# B293A_CoX_Amp_Top.net
KiCad netlist of a schematic drawn in Altium Designer
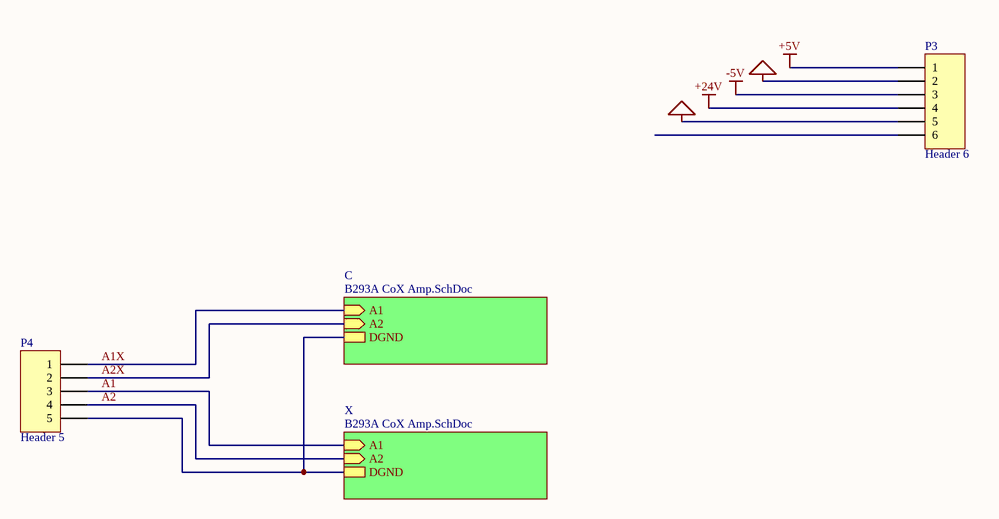
[diagram p0: B293A CoX Amp Top.SchDoc]

(export (version "E")
  (design (tool "Eeschema 10.0.6"))
  (components
    (comp (ref "P3")
      (value "Header 6")
      (footprint "SL 6W Vertical with latch")
      (description "Header, 6-Pin")
      (fields (field (name "PUBLISHER") "Altium Limited"))
      (libsource (lib "Miscellaneous Connectors") (part "Header 6"))
    )
    (comp (ref "P4")
      (value "Header 5")
      (footprint "SL 5W Vertical with latch")
      (description "Header, 5-Pin")
      (fields (field (name "PUBLISHER") "Altium Limited"))
      (libsource (lib "Miscellaneous Connectors") (part "Header 5"))
    )
  )
  (nets
    (net (code "1") (name "+5V") (class "Default")
      (node (ref "P3") (pin "1") (pinfunction "1_1") (pintype "passive"))
    )
    (net (code "2") (name "+24V") (class "Default")
      (node (ref "P3") (pin "4") (pinfunction "4_4") (pintype "passive"))
    )
    (net (code "3") (name "-5V") (class "Default")
      (node (ref "P3") (pin "3") (pinfunction "3_3") (pintype "passive"))
    )
    (net (code "4") (name "/A1") (class "Default")
      (node (ref "P4") (pin "3") (pinfunction "3_3") (pintype "passive"))
    )
    (net (code "5") (name "/A1X") (class "Default")
      (node (ref "P4") (pin "1") (pinfunction "1_1") (pintype "passive"))
    )
    (net (code "6") (name "/A2") (class "Default")
      (node (ref "P4") (pin "4") (pinfunction "4_4") (pintype "passive"))
    )
    (net (code "7") (name "/A2X") (class "Default")
      (node (ref "P4") (pin "2") (pinfunction "2_2") (pintype "passive"))
    )
    (net (code "8") (name "/DGND") (class "Default")
      (node (ref "P4") (pin "5") (pinfunction "5_5") (pintype "passive"))
    )
    (net (code "9") (name "GND") (class "Default")
      (node (ref "P3") (pin "2") (pinfunction "2_2") (pintype "passive"))
      (node (ref "P3") (pin "5") (pinfunction "5_5") (pintype "passive"))
    )
    (net (code "10") (name "unconnected-(P3-Pad6)") (class "Default")
      (node (ref "P3") (pin "6") (pinfunction "6_6") (pintype "passive"))
    )
  )
)
